# LedTester.net
KiCad netlist of a schematic drawn in EAGLE
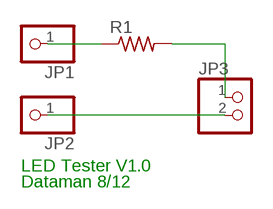
[diagram p0: schematic, sheet 1]

(export (version "E")
  (design (tool "Eeschema 10.0.6"))
  (components
    (comp (ref "JP1")
      (value "PINHD-1X1")
      (footprint "eagle-import:1X01")
      (libsource (lib "eagle-import") (part "PINHD-1X1"))
    )
    (comp (ref "JP2")
      (value "PINHD-1X1")
      (footprint "eagle-import:1X01")
      (libsource (lib "eagle-import") (part "PINHD-1X1"))
    )
    (comp (ref "JP3")
      (value "PINHD-1X2")
      (footprint "eagle-import:1X02")
      (libsource (lib "eagle-import") (part "PINHD-1X2"))
    )
    (comp (ref "R1")
      (value "R-US_0207/10")
      (footprint "eagle-import:0207_10")
      (libsource (lib "eagle-import") (part "R-US_0207/10"))
    )
  )
  (nets
    (net (code "1") (name "Net-(JP1-Pad1)") (class "Default")
      (node (ref "JP1") (pin "1") (pinfunction "1_1") (pintype "passive"))
      (node (ref "R1") (pin "1") (pinfunction "1_1") (pintype "passive"))
    )
    (net (code "2") (name "Net-(JP2-Pad1)") (class "Default")
      (node (ref "JP2") (pin "1") (pinfunction "1_1") (pintype "passive"))
      (node (ref "JP3") (pin "2") (pinfunction "2_2") (pintype "passive"))
    )
    (net (code "3") (name "Net-(JP3-Pad1)") (class "Default")
      (node (ref "JP3") (pin "1") (pinfunction "1_1") (pintype "passive"))
      (node (ref "R1") (pin "2") (pinfunction "2_2") (pintype "passive"))
    )
  )
)
